# Connection_of_encoders.net
KiCad netlist of a schematic drawn in Altium Designer
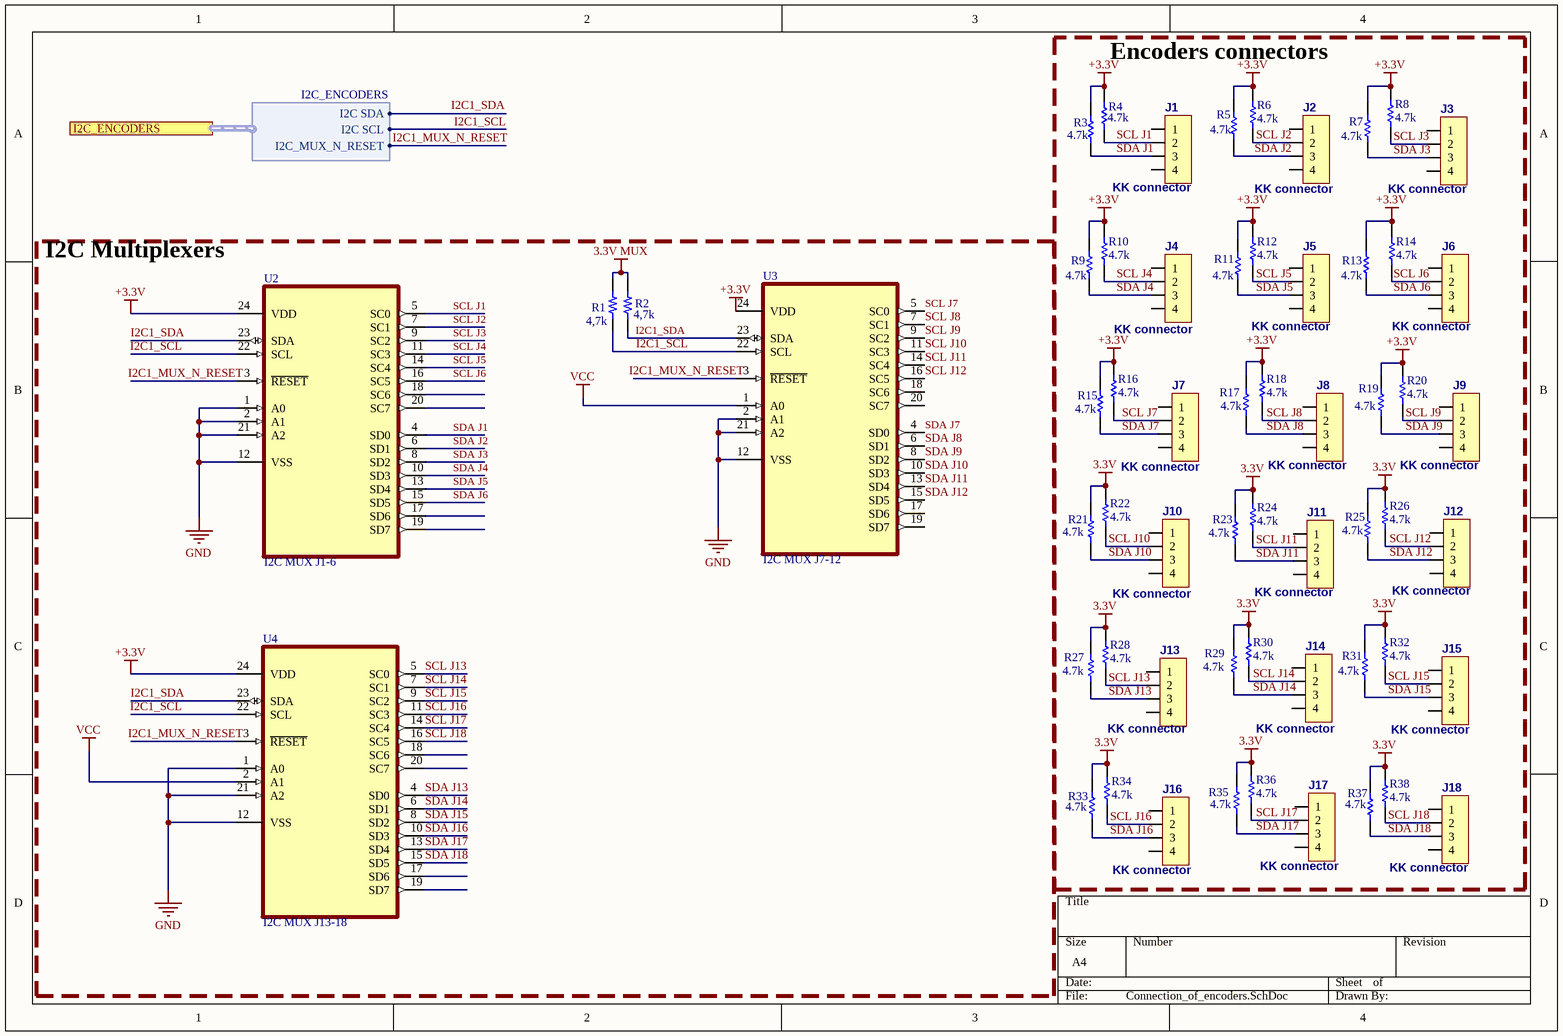
[diagram p0: Connection_of_encoders.SchDoc]

(export (version "E")
  (design (tool "Eeschema 10.0.6"))
  (components
    (comp (ref "J1")
      (value "KK connector")
      (footprint "KK/2.54/4")
      (description "Connector: PCB-cable; KK; socket; male; PIN:4; straight/right-angle; tinned; THT")
      (libsource (lib "kk") (part "CN_4x1"))
    )
    (comp (ref "J2")
      (value "KK connector")
      (footprint "KK/2.54/4")
      (description "Connector: PCB-cable; KK; socket; male; PIN:4; straight/right-angle; tinned; THT")
      (libsource (lib "kk") (part "CN_4x1"))
    )
    (comp (ref "J3")
      (value "KK connector")
      (footprint "KK/2.54/4")
      (description "Connector: PCB-cable; KK; socket; male; PIN:4; straight/right-angle; tinned; THT")
      (libsource (lib "kk") (part "CN_4x1"))
    )
    (comp (ref "J4")
      (value "KK connector")
      (footprint "KK/2.54/4")
      (description "Connector: PCB-cable; KK; socket; male; PIN:4; straight/right-angle; tinned; THT")
      (libsource (lib "kk") (part "CN_4x1"))
    )
    (comp (ref "J5")
      (value "KK connector")
      (footprint "KK/2.54/4")
      (description "Connector: PCB-cable; KK; socket; male; PIN:4; straight/right-angle; tinned; THT")
      (libsource (lib "kk") (part "CN_4x1"))
    )
    (comp (ref "J6")
      (value "KK connector")
      (footprint "KK/2.54/4")
      (description "Connector: PCB-cable; KK; socket; male; PIN:4; straight/right-angle; tinned; THT")
      (libsource (lib "kk") (part "CN_4x1"))
    )
    (comp (ref "J7")
      (value "KK connector")
      (footprint "KK/2.54/4")
      (description "Connector: PCB-cable; KK; socket; male; PIN:4; straight/right-angle; tinned; THT")
      (libsource (lib "kk") (part "CN_4x1"))
    )
    (comp (ref "J8")
      (value "KK connector")
      (footprint "KK/2.54/4")
      (description "Connector: PCB-cable; KK; socket; male; PIN:4; straight/right-angle; tinned; THT")
      (libsource (lib "kk") (part "CN_4x1"))
    )
    (comp (ref "J9")
      (value "KK connector")
      (footprint "KK/2.54/4")
      (description "Connector: PCB-cable; KK; socket; male; PIN:4; straight/right-angle; tinned; THT")
      (libsource (lib "kk") (part "CN_4x1"))
    )
    (comp (ref "J10")
      (value "KK connector")
      (footprint "KK/2.54/4")
      (description "Connector: PCB-cable; KK; socket; male; PIN:4; straight/right-angle; tinned; THT")
      (libsource (lib "kk") (part "CN_4x1"))
    )
    (comp (ref "J11")
      (value "KK connector")
      (footprint "KK/2.54/4")
      (description "Connector: PCB-cable; KK; socket; male; PIN:4; straight/right-angle; tinned; THT")
      (libsource (lib "kk") (part "CN_4x1"))
    )
    (comp (ref "J12")
      (value "KK connector")
      (footprint "KK/2.54/4")
      (description "Connector: PCB-cable; KK; socket; male; PIN:4; straight/right-angle; tinned; THT")
      (libsource (lib "kk") (part "CN_4x1"))
    )
    (comp (ref "J13")
      (value "KK connector")
      (footprint "KK/2.54/4")
      (description "Connector: PCB-cable; KK; socket; male; PIN:4; straight/right-angle; tinned; THT")
      (libsource (lib "kk") (part "CN_4x1"))
    )
    (comp (ref "J14")
      (value "KK connector")
      (footprint "KK/2.54/4")
      (description "Connector: PCB-cable; KK; socket; male; PIN:4; straight/right-angle; tinned; THT")
      (libsource (lib "kk") (part "CN_4x1"))
    )
    (comp (ref "J15")
      (value "KK connector")
      (footprint "KK/2.54/4")
      (description "Connector: PCB-cable; KK; socket; male; PIN:4; straight/right-angle; tinned; THT")
      (libsource (lib "kk") (part "CN_4x1"))
    )
    (comp (ref "J16")
      (value "KK connector")
      (footprint "KK/2.54/4")
      (description "Connector: PCB-cable; KK; socket; male; PIN:4; straight/right-angle; tinned; THT")
      (libsource (lib "kk") (part "CN_4x1"))
    )
    (comp (ref "J17")
      (value "KK connector")
      (footprint "KK/2.54/4")
      (description "Connector: PCB-cable; KK; socket; male; PIN:4; straight/right-angle; tinned; THT")
      (libsource (lib "kk") (part "CN_4x1"))
    )
    (comp (ref "J18")
      (value "KK connector")
      (footprint "KK/2.54/4")
      (description "Connector: PCB-cable; KK; socket; male; PIN:4; straight/right-angle; tinned; THT")
      (libsource (lib "kk") (part "CN_4x1"))
    )
    (comp (ref "R1")
      (value "4,7k")
      (footprint "RES 0603_1608")
      (description "RES 4,7K OHM 1% 0,1W 0603")
      (fields
        (field (name "PART NUMBER") "RNCS0603BKE10K0")
        (field (name "MANUFACTURER") "Stackpole Electronics Inc")
      )
      (libsource (lib "Celestial Altium Library - altium_library") (part "Resistor"))
    )
    (comp (ref "R2")
      (value "4,7k")
      (footprint "RES 0603_1608")
      (description "RES 4,7K OHM 1% 0,1W 0603")
      (fields
        (field (name "PART NUMBER") "RNCS0603BKE10K0")
        (field (name "MANUFACTURER") "Stackpole Electronics Inc")
      )
      (libsource (lib "Celestial Altium Library - altium_library") (part "Resistor"))
    )
    (comp (ref "R3")
      (value "4.7k")
      (footprint "RESC1609X50X30ML10T20")
      (description "RES 4,7K OHM 1% 0,1W 0603 RNCS0603BKE10K0")
      (fields (field (name "PART NUMBER") "CRCW060311K0FKEA") (field (name "MANUFACTURER") "Vishay Dale"))
      (libsource (lib "Altium Content Vault") (part "RES"))
    )
    (comp (ref "R4")
      (value "4.7k")
      (footprint "RESC1609X50X30ML10T20")
      (description "RES 4,7K OHM 1% 0,1W 0603 RNCS0603BKE10K0")
      (fields (field (name "PART NUMBER") "CRCW060311K0FKEA") (field (name "MANUFACTURER") "Vishay Dale"))
      (libsource (lib "Altium Content Vault") (part "RES"))
    )
    (comp (ref "R5")
      (value "4.7k")
      (footprint "RESC1609X50X30ML10T20")
      (description "RES 4,7K OHM 1% 0,1W 0603 RNCS0603BKE10K0")
      (fields (field (name "PART NUMBER") "CRCW060311K0FKEA") (field (name "MANUFACTURER") "Vishay Dale"))
      (libsource (lib "Altium Content Vault") (part "RES"))
    )
    (comp (ref "R6")
      (value "4.7k")
      (footprint "RESC1609X50X30ML10T20")
      (description "RES 4,7K OHM 1% 0,1W 0603 RNCS0603BKE10K0")
      (fields (field (name "PART NUMBER") "CRCW060311K0FKEA") (field (name "MANUFACTURER") "Vishay Dale"))
      (libsource (lib "Altium Content Vault") (part "RES"))
    )
    (comp (ref "R7")
      (value "4.7k")
      (footprint "RESC1609X50X30ML10T20")
      (description "RES 4,7K OHM 1% 0,1W 0603 RNCS0603BKE10K0")
      (fields (field (name "PART NUMBER") "CRCW060311K0FKEA") (field (name "MANUFACTURER") "Vishay Dale"))
      (libsource (lib "Altium Content Vault") (part "RES"))
    )
    (comp (ref "R8")
      (value "4.7k")
      (footprint "RESC1609X50X30ML10T20")
      (description "RES 4,7K OHM 1% 0,1W 0603 RNCS0603BKE10K0")
      (fields (field (name "PART NUMBER") "CRCW060311K0FKEA") (field (name "MANUFACTURER") "Vishay Dale"))
      (libsource (lib "Altium Content Vault") (part "RES"))
    )
    (comp (ref "R9")
      (value "4.7k")
      (footprint "RESC1609X50X30ML10T20")
      (description "RES 4,7K OHM 1% 0,1W 0603 RNCS0603BKE10K0")
      (fields (field (name "PART NUMBER") "CRCW060311K0FKEA") (field (name "MANUFACTURER") "Vishay Dale"))
      (libsource (lib "Altium Content Vault") (part "RES"))
    )
    (comp (ref "R10")
      (value "4.7k")
      (footprint "RESC1609X50X30ML10T20")
      (description "RES 4,7K OHM 1% 0,1W 0603 RNCS0603BKE10K0")
      (fields (field (name "PART NUMBER") "CRCW060311K0FKEA") (field (name "MANUFACTURER") "Vishay Dale"))
      (libsource (lib "Altium Content Vault") (part "RES"))
    )
    (comp (ref "R11")
      (value "4.7k")
      (footprint "RESC1609X50X30ML10T20")
      (description "RES 4,7K OHM 1% 0,1W 0603 RNCS0603BKE10K0")
      (fields (field (name "PART NUMBER") "CRCW060311K0FKEA") (field (name "MANUFACTURER") "Vishay Dale"))
      (libsource (lib "Altium Content Vault") (part "RES"))
    )
    (comp (ref "R12")
      (value "4.7k")
      (footprint "RESC1609X50X30ML10T20")
      (description "RES 4,7K OHM 1% 0,1W 0603 RNCS0603BKE10K0")
      (fields (field (name "PART NUMBER") "CRCW060311K0FKEA") (field (name "MANUFACTURER") "Vishay Dale"))
      (libsource (lib "Altium Content Vault") (part "RES"))
    )
    (comp (ref "R13")
      (value "4.7k")
      (footprint "RESC1609X50X30ML10T20")
      (description "RES 4,7K OHM 1% 0,1W 0603 RNCS0603BKE10K0")
      (fields (field (name "PART NUMBER") "CRCW060311K0FKEA") (field (name "MANUFACTURER") "Vishay Dale"))
      (libsource (lib "Altium Content Vault") (part "RES"))
    )
    (comp (ref "R14")
      (value "4.7k")
      (footprint "RESC1609X50X30ML10T20")
      (description "RES 4,7K OHM 1% 0,1W 0603 RNCS0603BKE10K0")
      (fields (field (name "PART NUMBER") "CRCW060311K0FKEA") (field (name "MANUFACTURER") "Vishay Dale"))
      (libsource (lib "Altium Content Vault") (part "RES"))
    )
    (comp (ref "R15")
      (value "4.7k")
      (footprint "RESC1609X50X30ML10T20")
      (description "RES 4,7K OHM 1% 0,1W 0603 RNCS0603BKE10K0")
      (fields (field (name "PART NUMBER") "CRCW060311K0FKEA") (field (name "MANUFACTURER") "Vishay Dale"))
      (libsource (lib "Altium Content Vault") (part "RES"))
    )
    (comp (ref "R16")
      (value "4.7k")
      (footprint "RESC1609X50X30ML10T20")
      (description "RES 4,7K OHM 1% 0,1W 0603 RNCS0603BKE10K0")
      (fields (field (name "PART NUMBER") "CRCW060311K0FKEA") (field (name "MANUFACTURER") "Vishay Dale"))
      (libsource (lib "Altium Content Vault") (part "RES"))
    )
    (comp (ref "R17")
      (value "4.7k")
      (footprint "RESC1609X50X30ML10T20")
      (description "RES 4,7K OHM 1% 0,1W 0603 RNCS0603BKE10K0")
      (fields (field (name "PART NUMBER") "CRCW060311K0FKEA") (field (name "MANUFACTURER") "Vishay Dale"))
      (libsource (lib "Altium Content Vault") (part "RES"))
    )
    (comp (ref "R18")
      (value "4.7k")
      (footprint "RESC1609X50X30ML10T20")
      (description "RES 4,7K OHM 1% 0,1W 0603 RNCS0603BKE10K0")
      (fields (field (name "PART NUMBER") "CRCW060311K0FKEA") (field (name "MANUFACTURER") "Vishay Dale"))
      (libsource (lib "Altium Content Vault") (part "RES"))
    )
    (comp (ref "R19")
      (value "4.7k")
      (footprint "RESC1609X50X30ML10T20")
      (description "RES 4,7K OHM 1% 0,1W 0603 RNCS0603BKE10K0")
      (fields (field (name "PART NUMBER") "CRCW060311K0FKEA") (field (name "MANUFACTURER") "Vishay Dale"))
      (libsource (lib "Altium Content Vault") (part "RES"))
    )
    (comp (ref "R20")
      (value "4.7k")
      (footprint "RESC1609X50X30ML10T20")
      (description "RES 4,7K OHM 1% 0,1W 0603 RNCS0603BKE10K0")
      (fields (field (name "PART NUMBER") "CRCW060311K0FKEA") (field (name "MANUFACTURER") "Vishay Dale"))
      (libsource (lib "Altium Content Vault") (part "RES"))
    )
    (comp (ref "R21")
      (value "4.7k")
      (footprint "RESC1609X50X30ML10T20")
      (description "RES 4,7K OHM 1% 0,1W 0603 RNCS0603BKE10K0")
      (fields (field (name "PART NUMBER") "CRCW060311K0FKEA") (field (name "MANUFACTURER") "Vishay Dale"))
      (libsource (lib "Altium Content Vault") (part "RES"))
    )
    (comp (ref "R22")
      (value "4.7k")
      (footprint "RESC1609X50X30ML10T20")
      (description "RES 4,7K OHM 1% 0,1W 0603 RNCS0603BKE10K0")
      (fields (field (name "PART NUMBER") "CRCW060311K0FKEA") (field (name "MANUFACTURER") "Vishay Dale"))
      (libsource (lib "Altium Content Vault") (part "RES"))
    )
    (comp (ref "R23")
      (value "4.7k")
      (footprint "RESC1609X50X30ML10T20")
      (description "RES 4,7K OHM 1% 0,1W 0603 RNCS0603BKE10K0")
      (fields (field (name "PART NUMBER") "CRCW060311K0FKEA") (field (name "MANUFACTURER") "Vishay Dale"))
      (libsource (lib "Altium Content Vault") (part "RES"))
    )
    (comp (ref "R24")
      (value "4.7k")
      (footprint "RESC1609X50X30ML10T20")
      (description "RES 4,7K OHM 1% 0,1W 0603 RNCS0603BKE10K0")
      (fields (field (name "PART NUMBER") "CRCW060311K0FKEA") (field (name "MANUFACTURER") "Vishay Dale"))
      (libsource (lib "Altium Content Vault") (part "RES"))
    )
    (comp (ref "R25")
      (value "4.7k")
      (footprint "RESC1609X50X30ML10T20")
      (description "RES 4,7K OHM 1% 0,1W 0603 RNCS0603BKE10K0")
      (fields (field (name "PART NUMBER") "CRCW060311K0FKEA") (field (name "MANUFACTURER") "Vishay Dale"))
      (libsource (lib "Altium Content Vault") (part "RES"))
    )
    (comp (ref "R26")
      (value "4.7k")
      (footprint "RESC1609X50X30ML10T20")
      (description "RES 4,7K OHM 1% 0,1W 0603 RNCS0603BKE10K0")
      (fields (field (name "PART NUMBER") "CRCW060311K0FKEA") (field (name "MANUFACTURER") "Vishay Dale"))
      (libsource (lib "Altium Content Vault") (part "RES"))
    )
    (comp (ref "R27")
      (value "4.7k")
      (footprint "RESC1609X50X30ML10T20")
      (description "RES 4,7K OHM 1% 0,1W 0603 RNCS0603BKE10K0")
      (fields (field (name "PART NUMBER") "CRCW060311K0FKEA") (field (name "MANUFACTURER") "Vishay Dale"))
      (libsource (lib "Altium Content Vault") (part "RES"))
    )
    (comp (ref "R28")
      (value "4.7k")
      (footprint "RESC1609X50X30ML10T20")
      (description "RES 4,7K OHM 1% 0,1W 0603 RNCS0603BKE10K0")
      (fields (field (name "PART NUMBER") "CRCW060311K0FKEA") (field (name "MANUFACTURER") "Vishay Dale"))
      (libsource (lib "Altium Content Vault") (part "RES"))
    )
    (comp (ref "R29")
      (value "4.7k")
      (footprint "RESC1609X50X30ML10T20")
      (description "RES 4,7K OHM 1% 0,1W 0603 RNCS0603BKE10K0")
      (fields (field (name "PART NUMBER") "CRCW060311K0FKEA") (field (name "MANUFACTURER") "Vishay Dale"))
      (libsource (lib "Altium Content Vault") (part "RES"))
    )
    (comp (ref "R30")
      (value "4.7k")
      (footprint "RESC1609X50X30ML10T20")
      (description "RES 4,7K OHM 1% 0,1W 0603 RNCS0603BKE10K0")
      (fields (field (name "PART NUMBER") "CRCW060311K0FKEA") (field (name "MANUFACTURER") "Vishay Dale"))
      (libsource (lib "Altium Content Vault") (part "RES"))
    )
    (comp (ref "R31")
      (value "4.7k")
      (footprint "RESC1609X50X30ML10T20")
      (description "RES 4,7K OHM 1% 0,1W 0603 RNCS0603BKE10K0")
      (fields (field (name "PART NUMBER") "CRCW060311K0FKEA") (field (name "MANUFACTURER") "Vishay Dale"))
      (libsource (lib "Altium Content Vault") (part "RES"))
    )
    (comp (ref "R32")
      (value "4.7k")
      (footprint "RESC1609X50X30ML10T20")
      (description "RES 4,7K OHM 1% 0,1W 0603 RNCS0603BKE10K0")
      (fields (field (name "PART NUMBER") "CRCW060311K0FKEA") (field (name "MANUFACTURER") "Vishay Dale"))
      (libsource (lib "Altium Content Vault") (part "RES"))
    )
    (comp (ref "R33")
      (value "4.7k")
      (footprint "RESC1609X50X30ML10T20")
      (description "RES 4,7K OHM 1% 0,1W 0603 RNCS0603BKE10K0")
      (fields (field (name "PART NUMBER") "CRCW060311K0FKEA") (field (name "MANUFACTURER") "Vishay Dale"))
      (libsource (lib "Altium Content Vault") (part "RES"))
    )
    (comp (ref "R34")
      (value "4.7k")
      (footprint "RESC1609X50X30ML10T20")
      (description "RES 4,7K OHM 1% 0,1W 0603 RNCS0603BKE10K0")
      (fields (field (name "PART NUMBER") "CRCW060311K0FKEA") (field (name "MANUFACTURER") "Vishay Dale"))
      (libsource (lib "Altium Content Vault") (part "RES"))
    )
    (comp (ref "R35")
      (value "4.7k")
      (footprint "RESC1609X50X30ML10T20")
      (description "RES 4,7K OHM 1% 0,1W 0603 RNCS0603BKE10K0")
      (fields (field (name "PART NUMBER") "CRCW060311K0FKEA") (field (name "MANUFACTURER") "Vishay Dale"))
      (libsource (lib "Altium Content Vault") (part "RES"))
    )
    (comp (ref "R36")
      (value "4.7k")
      (footprint "RESC1609X50X30ML10T20")
      (description "RES 4,7K OHM 1% 0,1W 0603 RNCS0603BKE10K0")
      (fields (field (name "PART NUMBER") "CRCW060311K0FKEA") (field (name "MANUFACTURER") "Vishay Dale"))
      (libsource (lib "Altium Content Vault") (part "RES"))
    )
    (comp (ref "R37")
      (value "4.7k")
      (footprint "RESC1609X50X30ML10T20")
      (description "RES 4,7K OHM 1% 0,1W 0603 RNCS0603BKE10K0")
      (fields (field (name "PART NUMBER") "CRCW060311K0FKEA") (field (name "MANUFACTURER") "Vishay Dale"))
      (libsource (lib "Altium Content Vault") (part "RES"))
    )
    (comp (ref "R38")
      (value "4.7k")
      (footprint "RESC1609X50X30ML10T20")
      (description "RES 4,7K OHM 1% 0,1W 0603 RNCS0603BKE10K0")
      (fields (field (name "PART NUMBER") "CRCW060311K0FKEA") (field (name "MANUFACTURER") "Vishay Dale"))
      (libsource (lib "Altium Content Vault") (part "RES"))
    )
    (comp (ref "U2")
      (value "I2C MUX J1-6")
      (footprint "SOP65P640X110-24N")
      (description "Translating Multiplexer Interface 24-TSSOP PCA9547PW,118")
      (fields (field (name "MP") "PCA9547PW,118") (field (name "MF") "NXP USA"))
      (libsource (lib "MyWorkspace") (part "PCA9547PW,118"))
    )
    (comp (ref "U3")
      (value "I2C MUX J7-12")
      (footprint "SOP65P640X110-24N")
      (description "Translating Multiplexer Interface 24-TSSOP PCA9547PW,118")
      (fields (field (name "MP") "PCA9547PW,118") (field (name "MF") "NXP USA"))
      (libsource (lib "MyWorkspace") (part "PCA9547PW,118"))
    )
    (comp (ref "U4")
      (value "I2C MUX J13-18")
      (footprint "SOP65P640X110-24N")
      (description "Translating Multiplexer Interface 24-TSSOP PCA9547PW")
      (fields (field (name "MP") "PCA9547PW,118") (field (name "MF") "NXP USA"))
      (libsource (lib "MyWorkspace") (part "PCA9547PW,118"))
    )
  )
  (nets
    (net (code "2") (name "+3.3V") (class "Default")
      (node (ref "R10") (pin "2") (pinfunction "2_2") (pintype "passive"))
      (node (ref "R11") (pin "2") (pinfunction "2_2") (pintype "passive"))
      (node (ref "R12") (pin "2") (pinfunction "2_2") (pintype "passive"))
      (node (ref "R13") (pin "2") (pinfunction "2_2") (pintype "passive"))
      (node (ref "R14") (pin "2") (pinfunction "2_2") (pintype "passive"))
      (node (ref "R15") (pin "2") (pinfunction "2_2") (pintype "passive"))
      (node (ref "R16") (pin "2") (pinfunction "2_2") (pintype "passive"))
      (node (ref "R17") (pin "2") (pinfunction "2_2") (pintype "passive"))
      (node (ref "R18") (pin "2") (pinfunction "2_2") (pintype "passive"))
      (node (ref "R19") (pin "2") (pinfunction "2_2") (pintype "passive"))
      (node (ref "R20") (pin "2") (pinfunction "2_2") (pintype "passive"))
      (node (ref "R3") (pin "2") (pinfunction "2_2") (pintype "passive"))
      (node (ref "R4") (pin "2") (pinfunction "2_2") (pintype "passive"))
      (node (ref "R5") (pin "2") (pinfunction "2_2") (pintype "passive"))
      (node (ref "R6") (pin "2") (pinfunction "2_2") (pintype "passive"))
      (node (ref "R7") (pin "2") (pinfunction "2_2") (pintype "passive"))
      (node (ref "R8") (pin "2") (pinfunction "2_2") (pintype "passive"))
      (node (ref "R9") (pin "2") (pinfunction "2_2") (pintype "passive"))
      (node (ref "U2") (pin "24") (pinfunction "VDD_24") (pintype "power_in"))
      (node (ref "U3") (pin "24") (pinfunction "VDD_24") (pintype "power_in"))
      (node (ref "U4") (pin "24") (pinfunction "VDD_24") (pintype "power_in"))
    )
    (net (code "3") (name "/I2C1_MUX_N_RESET") (class "Default")
      (node (ref "U2") (pin "3") (pinfunction "~{RESET}_3") (pintype "input"))
      (node (ref "U3") (pin "3") (pinfunction "~{RESET}_3") (pintype "input"))
      (node (ref "U4") (pin "3") (pinfunction "~{RESET}_3") (pintype "input"))
    )
    (net (code "4") (name "/I2C1_SCL") (class "Default")
      (node (ref "R1") (pin "2") (pinfunction "2_2") (pintype "passive"))
      (node (ref "U2") (pin "22") (pinfunction "SCL_22") (pintype "input"))
      (node (ref "U3") (pin "22") (pinfunction "SCL_22") (pintype "input"))
      (node (ref "U4") (pin "22") (pinfunction "SCL_22") (pintype "input"))
    )
    (net (code "5") (name "/I2C1_SDA") (class "Default")
      (node (ref "R2") (pin "2") (pinfunction "2_2") (pintype "passive"))
      (node (ref "U2") (pin "23") (pinfunction "SDA_23") (pintype "bidirectional"))
      (node (ref "U3") (pin "23") (pinfunction "SDA_23") (pintype "bidirectional"))
      (node (ref "U4") (pin "23") (pinfunction "SDA_23") (pintype "bidirectional"))
    )
    (net (code "6") (name "/SCL J1") (class "Default")
      (node (ref "J1") (pin "2") (pinfunction "2_2") (pintype "passive"))
      (node (ref "R4") (pin "1") (pinfunction "1_1") (pintype "passive"))
      (node (ref "U2") (pin "5") (pinfunction "SC0_5") (pintype "output"))
    )
    (net (code "7") (name "/SCL J2") (class "Default")
      (node (ref "J2") (pin "2") (pinfunction "2_2") (pintype "passive"))
      (node (ref "R6") (pin "1") (pinfunction "1_1") (pintype "passive"))
      (node (ref "U2") (pin "7") (pinfunction "SC1_7") (pintype "output"))
    )
    (net (code "8") (name "/SCL J3") (class "Default")
      (node (ref "J3") (pin "2") (pinfunction "2_2") (pintype "passive"))
      (node (ref "R8") (pin "1") (pinfunction "1_1") (pintype "passive"))
      (node (ref "U2") (pin "9") (pinfunction "SC2_9") (pintype "output"))
    )
    (net (code "9") (name "/SCL J4") (class "Default")
      (node (ref "J4") (pin "2") (pinfunction "2_2") (pintype "passive"))
      (node (ref "R10") (pin "1") (pinfunction "1_1") (pintype "passive"))
      (node (ref "U2") (pin "11") (pinfunction "SC3_11") (pintype "output"))
    )
    (net (code "10") (name "/SCL J5") (class "Default")
      (node (ref "J5") (pin "2") (pinfunction "2_2") (pintype "passive"))
      (node (ref "R12") (pin "1") (pinfunction "1_1") (pintype "passive"))
      (node (ref "U2") (pin "14") (pinfunction "SC4_14") (pintype "output"))
    )
    (net (code "11") (name "/SCL J6") (class "Default")
      (node (ref "J6") (pin "2") (pinfunction "2_2") (pintype "passive"))
      (node (ref "R14") (pin "1") (pinfunction "1_1") (pintype "passive"))
      (node (ref "U2") (pin "16") (pinfunction "SC5_16") (pintype "output"))
    )
    (net (code "12") (name "/SCL J7") (class "Default")
      (node (ref "J7") (pin "2") (pinfunction "2_2") (pintype "passive"))
      (node (ref "R16") (pin "1") (pinfunction "1_1") (pintype "passive"))
      (node (ref "U3") (pin "5") (pinfunction "SC0_5") (pintype "output"))
    )
    (net (code "13") (name "/SCL J8") (class "Default")
      (node (ref "J8") (pin "2") (pinfunction "2_2") (pintype "passive"))
      (node (ref "R18") (pin "1") (pinfunction "1_1") (pintype "passive"))
      (node (ref "U3") (pin "7") (pinfunction "SC1_7") (pintype "output"))
    )
    (net (code "14") (name "/SCL J9") (class "Default")
      (node (ref "J9") (pin "2") (pinfunction "2_2") (pintype "passive"))
      (node (ref "R20") (pin "1") (pinfunction "1_1") (pintype "passive"))
      (node (ref "U3") (pin "9") (pinfunction "SC2_9") (pintype "output"))
    )
    (net (code "15") (name "/SCL J10") (class "Default")
      (node (ref "J10") (pin "2") (pinfunction "2_2") (pintype "passive"))
      (node (ref "R22") (pin "1") (pinfunction "1_1") (pintype "passive"))
      (node (ref "U3") (pin "11") (pinfunction "SC3_11") (pintype "output"))
    )
    (net (code "16") (name "/SCL J11") (class "Default")
      (node (ref "J11") (pin "2") (pinfunction "2_2") (pintype "passive"))
      (node (ref "R24") (pin "1") (pinfunction "1_1") (pintype "passive"))
      (node (ref "U3") (pin "14") (pinfunction "SC4_14") (pintype "output"))
    )
    (net (code "17") (name "/SCL J12") (class "Default")
      (node (ref "J12") (pin "2") (pinfunction "2_2") (pintype "passive"))
      (node (ref "R26") (pin "1") (pinfunction "1_1") (pintype "passive"))
      (node (ref "U3") (pin "16") (pinfunction "SC5_16") (pintype "output"))
    )
    (net (code "18") (name "/SCL J13") (class "Default")
      (node (ref "J13") (pin "2") (pinfunction "2_2") (pintype "passive"))
      (node (ref "R28") (pin "1") (pinfunction "1_1") (pintype "passive"))
      (node (ref "U4") (pin "5") (pinfunction "SC0_5") (pintype "output"))
    )
    (net (code "19") (name "/SCL J14") (class "Default")
      (node (ref "J14") (pin "2") (pinfunction "2_2") (pintype "passive"))
      (node (ref "R30") (pin "1") (pinfunction "1_1") (pintype "passive"))
      (node (ref "U4") (pin "7") (pinfunction "SC1_7") (pintype "output"))
    )
    (net (code "20") (name "/SCL J15") (class "Default")
      (node (ref "J15") (pin "2") (pinfunction "2_2") (pintype "passive"))
      (node (ref "R32") (pin "1") (pinfunction "1_1") (pintype "passive"))
      (node (ref "U4") (pin "9") (pinfunction "SC2_9") (pintype "output"))
    )
    (net (code "21") (name "/SCL J16") (class "Default")
      (node (ref "J16") (pin "2") (pinfunction "2_2") (pintype "passive"))
      (node (ref "R34") (pin "1") (pinfunction "1_1") (pintype "passive"))
      (node (ref "U4") (pin "11") (pinfunction "SC3_11") (pintype "output"))
    )
    (net (code "22") (name "/SCL J17") (class "Default")
      (node (ref "J17") (pin "2") (pinfunction "2_2") (pintype "passive"))
      (node (ref "R36") (pin "1") (pinfunction "1_1") (pintype "passive"))
      (node (ref "U4") (pin "14") (pinfunction "SC4_14") (pintype "output"))
    )
    (net (code "23") (name "/SCL J18") (class "Default")
      (node (ref "J18") (pin "2") (pinfunction "2_2") (pintype "passive"))
      (node (ref "R38") (pin "1") (pinfunction "1_1") (pintype "passive"))
      (node (ref "U4") (pin "16") (pinfunction "SC5_16") (pintype "output"))
    )
    (net (code "24") (name "/SDA J1") (class "Default")
      (node (ref "J1") (pin "3") (pinfunction "3_3") (pintype "passive"))
      (node (ref "R3") (pin "1") (pinfunction "1_1") (pintype "passive"))
      (node (ref "U2") (pin "4") (pinfunction "SD0_4") (pintype "output"))
    )
    (net (code "25") (name "/SDA J2") (class "Default")
      (node (ref "J2") (pin "3") (pinfunction "3_3") (pintype "passive"))
      (node (ref "R5") (pin "1") (pinfunction "1_1") (pintype "passive"))
      (node (ref "U2") (pin "6") (pinfunction "SD1_6") (pintype "output"))
    )
    (net (code "26") (name "/SDA J3") (class "Default")
      (node (ref "J3") (pin "3") (pinfunction "3_3") (pintype "passive"))
      (node (ref "R7") (pin "1") (pinfunction "1_1") (pintype "passive"))
      (node (ref "U2") (pin "8") (pinfunction "SD2_8") (pintype "output"))
    )
    (net (code "27") (name "/SDA J4") (class "Default")
      (node (ref "J4") (pin "3") (pinfunction "3_3") (pintype "passive"))
      (node (ref "R9") (pin "1") (pinfunction "1_1") (pintype "passive"))
      (node (ref "U2") (pin "10") (pinfunction "SD3_10") (pintype "output"))
    )
    (net (code "28") (name "/SDA J5") (class "Default")
      (node (ref "J5") (pin "3") (pinfunction "3_3") (pintype "passive"))
      (node (ref "R11") (pin "1") (pinfunction "1_1") (pintype "passive"))
      (node (ref "U2") (pin "13") (pinfunction "SD4_13") (pintype "output"))
    )
    (net (code "29") (name "/SDA J6") (class "Default")
      (node (ref "J6") (pin "3") (pinfunction "3_3") (pintype "passive"))
      (node (ref "R13") (pin "1") (pinfunction "1_1") (pintype "passive"))
      (node (ref "U2") (pin "15") (pinfunction "SD5_15") (pintype "output"))
    )
    (net (code "30") (name "/SDA J7") (class "Default")
      (node (ref "J7") (pin "3") (pinfunction "3_3") (pintype "passive"))
      (node (ref "R15") (pin "1") (pinfunction "1_1") (pintype "passive"))
      (node (ref "U3") (pin "4") (pinfunction "SD0_4") (pintype "output"))
    )
    (net (code "31") (name "/SDA J8") (class "Default")
      (node (ref "J8") (pin "3") (pinfunction "3_3") (pintype "passive"))
      (node (ref "R17") (pin "1") (pinfunction "1_1") (pintype "passive"))
      (node (ref "U3") (pin "6") (pinfunction "SD1_6") (pintype "output"))
    )
    (net (code "32") (name "/SDA J9") (class "Default")
      (node (ref "J9") (pin "3") (pinfunction "3_3") (pintype "passive"))
      (node (ref "R19") (pin "1") (pinfunction "1_1") (pintype "passive"))
      (node (ref "U3") (pin "8") (pinfunction "SD2_8") (pintype "output"))
    )
    (net (code "33") (name "/SDA J10") (class "Default")
      (node (ref "J10") (pin "3") (pinfunction "3_3") (pintype "passive"))
      (node (ref "R21") (pin "1") (pinfunction "1_1") (pintype "passive"))
      (node (ref "U3") (pin "10") (pinfunction "SD3_10") (pintype "output"))
    )
    (net (code "34") (name "/SDA J11") (class "Default")
      (node (ref "J11") (pin "3") (pinfunction "3_3") (pintype "passive"))
      (node (ref "R23") (pin "1") (pinfunction "1_1") (pintype "passive"))
      (node (ref "U3") (pin "13") (pinfunction "SD4_13") (pintype "output"))
    )
    (net (code "35") (name "/SDA J12") (class "Default")
      (node (ref "J12") (pin "3") (pinfunction "3_3") (pintype "passive"))
      (node (ref "R25") (pin "1") (pinfunction "1_1") (pintype "passive"))
      (node (ref "U3") (pin "15") (pinfunction "SD5_15") (pintype "output"))
    )
    (net (code "36") (name "/SDA J13") (class "Default")
      (node (ref "J13") (pin "3") (pinfunction "3_3") (pintype "passive"))
      (node (ref "R27") (pin "1") (pinfunction "1_1") (pintype "passive"))
      (node (ref "U4") (pin "4") (pinfunction "SD0_4") (pintype "output"))
    )
    (net (code "37") (name "/SDA J14") (class "Default")
      (node (ref "J14") (pin "3") (pinfunction "3_3") (pintype "passive"))
      (node (ref "R29") (pin "1") (pinfunction "1_1") (pintype "passive"))
      (node (ref "U4") (pin "6") (pinfunction "SD1_6") (pintype "output"))
    )
    (net (code "38") (name "/SDA J15") (class "Default")
      (node (ref "J15") (pin "3") (pinfunction "3_3") (pintype "passive"))
      (node (ref "R31") (pin "1") (pinfunction "1_1") (pintype "passive"))
      (node (ref "U4") (pin "8") (pinfunction "SD2_8") (pintype "output"))
    )
    (net (code "39") (name "/SDA J16") (class "Default")
      (node (ref "J16") (pin "3") (pinfunction "3_3") (pintype "passive"))
      (node (ref "R33") (pin "1") (pinfunction "1_1") (pintype "passive"))
      (node (ref "U4") (pin "10") (pinfunction "SD3_10") (pintype "output"))
    )
    (net (code "40") (name "/SDA J17") (class "Default")
      (node (ref "J17") (pin "3") (pinfunction "3_3") (pintype "passive"))
      (node (ref "R35") (pin "1") (pinfunction "1_1") (pintype "passive"))
      (node (ref "U4") (pin "13") (pinfunction "SD4_13") (pintype "output"))
    )
    (net (code "41") (name "/SDA J18") (class "Default")
      (node (ref "J18") (pin "3") (pinfunction "3_3") (pintype "passive"))
      (node (ref "R37") (pin "1") (pinfunction "1_1") (pintype "passive"))
      (node (ref "U4") (pin "15") (pinfunction "SD5_15") (pintype "output"))
    )
    (net (code "43") (name "3.3V") (class "Default")
      (node (ref "R21") (pin "2") (pinfunction "2_2") (pintype "passive"))
      (node (ref "R22") (pin "2") (pinfunction "2_2") (pintype "passive"))
      (node (ref "R23") (pin "2") (pinfunction "2_2") (pintype "passive"))
      (node (ref "R24") (pin "2") (pinfunction "2_2") (pintype "passive"))
      (node (ref "R25") (pin "2") (pinfunction "2_2") (pintype "passive"))
      (node (ref "R26") (pin "2") (pinfunction "2_2") (pintype "passive"))
      (node (ref "R27") (pin "2") (pinfunction "2_2") (pintype "passive"))
      (node (ref "R28") (pin "2") (pinfunction "2_2") (pintype "passive"))
      (node (ref "R29") (pin "2") (pinfunction "2_2") (pintype "passive"))
      (node (ref "R30") (pin "2") (pinfunction "2_2") (pintype "passive"))
      (node (ref "R31") (pin "2") (pinfunction "2_2") (pintype "passive"))
      (node (ref "R32") (pin "2") (pinfunction "2_2") (pintype "passive"))
      (node (ref "R33") (pin "2") (pinfunction "2_2") (pintype "passive"))
      (node (ref "R34") (pin "2") (pinfunction "2_2") (pintype "passive"))
      (node (ref "R35") (pin "2") (pinfunction "2_2") (pintype "passive"))
      (node (ref "R36") (pin "2") (pinfunction "2_2") (pintype "passive"))
      (node (ref "R37") (pin "2") (pinfunction "2_2") (pintype "passive"))
      (node (ref "R38") (pin "2") (pinfunction "2_2") (pintype "passive"))
    )
    (net (code "44") (name "3.3V MUX") (class "Default")
      (node (ref "R1") (pin "1") (pinfunction "1_1") (pintype "passive"))
      (node (ref "R2") (pin "1") (pinfunction "1_1") (pintype "passive"))
    )
    (net (code "45") (name "GND") (class "Default")
      (node (ref "U2") (pin "1") (pinfunction "A0_1") (pintype "input"))
      (node (ref "U2") (pin "12") (pinfunction "VSS_12") (pintype "passive"))
      (node (ref "U2") (pin "2") (pinfunction "A1_2") (pintype "input"))
      (node (ref "U2") (pin "21") (pinfunction "A2_21") (pintype "input"))
      (node (ref "U3") (pin "12") (pinfunction "VSS_12") (pintype "passive"))
      (node (ref "U3") (pin "2") (pinfunction "A1_2") (pintype "input"))
      (node (ref "U3") (pin "21") (pinfunction "A2_21") (pintype "input"))
      (node (ref "U4") (pin "1") (pinfunction "A0_1") (pintype "input"))
      (node (ref "U4") (pin "12") (pinfunction "VSS_12") (pintype "passive"))
      (node (ref "U4") (pin "21") (pinfunction "A2_21") (pintype "input"))
    )
    (net (code "46") (name "VCC") (class "Default")
      (node (ref "U3") (pin "1") (pinfunction "A0_1") (pintype "input"))
      (node (ref "U4") (pin "2") (pinfunction "A1_2") (pintype "input"))
    )
    (net (code "47") (name "unconnected-(J1-Pad1)") (class "Default")
      (node (ref "J1") (pin "1") (pinfunction "1_1") (pintype "passive"))
    )
    (net (code "48") (name "unconnected-(J1-Pad4)") (class "Default")
      (node (ref "J1") (pin "4") (pinfunction "4_4") (pintype "passive"))
    )
    (net (code "49") (name "unconnected-(J2-Pad1)") (class "Default")
      (node (ref "J2") (pin "1") (pinfunction "1_1") (pintype "passive"))
    )
    (net (code "50") (name "unconnected-(J2-Pad4)") (class "Default")
      (node (ref "J2") (pin "4") (pinfunction "4_4") (pintype "passive"))
    )
    (net (code "51") (name "unconnected-(J3-Pad1)") (class "Default")
      (node (ref "J3") (pin "1") (pinfunction "1_1") (pintype "passive"))
    )
    (net (code "52") (name "unconnected-(J3-Pad4)") (class "Default")
      (node (ref "J3") (pin "4") (pinfunction "4_4") (pintype "passive"))
    )
    (net (code "53") (name "unconnected-(J4-Pad1)") (class "Default")
      (node (ref "J4") (pin "1") (pinfunction "1_1") (pintype "passive"))
    )
    (net (code "54") (name "unconnected-(J4-Pad4)") (class "Default")
      (node (ref "J4") (pin "4") (pinfunction "4_4") (pintype "passive"))
    )
    (net (code "55") (name "unconnected-(J5-Pad1)") (class "Default")
      (node (ref "J5") (pin "1") (pinfunction "1_1") (pintype "passive"))
    )
    (net (code "56") (name "unconnected-(J5-Pad4)") (class "Default")
      (node (ref "J5") (pin "4") (pinfunction "4_4") (pintype "passive"))
    )
    (net (code "57") (name "unconnected-(J6-Pad1)") (class "Default")
      (node (ref "J6") (pin "1") (pinfunction "1_1") (pintype "passive"))
    )
    (net (code "58") (name "unconnected-(J6-Pad4)") (class "Default")
      (node (ref "J6") (pin "4") (pinfunction "4_4") (pintype "passive"))
    )
    (net (code "59") (name "unconnected-(J7-Pad1)") (class "Default")
      (node (ref "J7") (pin "1") (pinfunction "1_1") (pintype "passive"))
    )
    (net (code "60") (name "unconnected-(J7-Pad4)") (class "Default")
      (node (ref "J7") (pin "4") (pinfunction "4_4") (pintype "passive"))
    )
    (net (code "61") (name "unconnected-(J8-Pad1)") (class "Default")
      (node (ref "J8") (pin "1") (pinfunction "1_1") (pintype "passive"))
    )
    (net (code "62") (name "unconnected-(J8-Pad4)") (class "Default")
      (node (ref "J8") (pin "4") (pinfunction "4_4") (pintype "passive"))
    )
    (net (code "63") (name "unconnected-(J9-Pad1)") (class "Default")
      (node (ref "J9") (pin "1") (pinfunction "1_1") (pintype "passive"))
    )
    (net (code "64") (name "unconnected-(J9-Pad4)") (class "Default")
      (node (ref "J9") (pin "4") (pinfunction "4_4") (pintype "passive"))
    )
    (net (code "65") (name "unconnected-(J10-Pad1)") (class "Default")
      (node (ref "J10") (pin "1") (pinfunction "1_1") (pintype "passive"))
    )
    (net (code "66") (name "unconnected-(J10-Pad4)") (class "Default")
      (node (ref "J10") (pin "4") (pinfunction "4_4") (pintype "passive"))
    )
    (net (code "67") (name "unconnected-(J11-Pad1)") (class "Default")
      (node (ref "J11") (pin "1") (pinfunction "1_1") (pintype "passive"))
    )
    (net (code "68") (name "unconnected-(J11-Pad4)") (class "Default")
      (node (ref "J11") (pin "4") (pinfunction "4_4") (pintype "passive"))
    )
    (net (code "69") (name "unconnected-(J12-Pad1)") (class "Default")
      (node (ref "J12") (pin "1") (pinfunction "1_1") (pintype "passive"))
    )
    (net (code "70") (name "unconnected-(J12-Pad4)") (class "Default")
      (node (ref "J12") (pin "4") (pinfunction "4_4") (pintype "passive"))
    )
    (net (code "71") (name "unconnected-(J13-Pad1)") (class "Default")
      (node (ref "J13") (pin "1") (pinfunction "1_1") (pintype "passive"))
    )
    (net (code "72") (name "unconnected-(J13-Pad4)") (class "Default")
      (node (ref "J13") (pin "4") (pinfunction "4_4") (pintype "passive"))
    )
    (net (code "73") (name "unconnected-(J14-Pad1)") (class "Default")
      (node (ref "J14") (pin "1") (pinfunction "1_1") (pintype "passive"))
    )
    (net (code "74") (name "unconnected-(J14-Pad4)") (class "Default")
      (node (ref "J14") (pin "4") (pinfunction "4_4") (pintype "passive"))
    )
    (net (code "75") (name "unconnected-(J15-Pad1)") (class "Default")
      (node (ref "J15") (pin "1") (pinfunction "1_1") (pintype "passive"))
    )
    (net (code "76") (name "unconnected-(J15-Pad4)") (class "Default")
      (node (ref "J15") (pin "4") (pinfunction "4_4") (pintype "passive"))
    )
    (net (code "77") (name "unconnected-(J16-Pad1)") (class "Default")
      (node (ref "J16") (pin "1") (pinfunction "1_1") (pintype "passive"))
    )
    (net (code "78") (name "unconnected-(J16-Pad4)") (class "Default")
      (node (ref "J16") (pin "4") (pinfunction "4_4") (pintype "passive"))
    )
    (net (code "79") (name "unconnected-(J17-Pad1)") (class "Default")
      (node (ref "J17") (pin "1") (pinfunction "1_1") (pintype "passive"))
    )
    (net (code "80") (name "unconnected-(J17-Pad4)") (class "Default")
      (node (ref "J17") (pin "4") (pinfunction "4_4") (pintype "passive"))
    )
    (net (code "81") (name "unconnected-(J18-Pad1)") (class "Default")
      (node (ref "J18") (pin "1") (pinfunction "1_1") (pintype "passive"))
    )
    (net (code "82") (name "unconnected-(J18-Pad4)") (class "Default")
      (node (ref "J18") (pin "4") (pinfunction "4_4") (pintype "passive"))
    )
    (net (code "83") (name "unconnected-(U2-SC6-Pad18)") (class "Default")
      (node (ref "U2") (pin "18") (pinfunction "SC6_18") (pintype "output"))
    )
    (net (code "84") (name "unconnected-(U2-SC7-Pad20)") (class "Default")
      (node (ref "U2") (pin "20") (pinfunction "SC7_20") (pintype "output"))
    )
    (net (code "85") (name "unconnected-(U2-SD6-Pad17)") (class "Default")
      (node (ref "U2") (pin "17") (pinfunction "SD6_17") (pintype "output"))
    )
    (net (code "86") (name "unconnected-(U2-SD7-Pad19)") (class "Default")
      (node (ref "U2") (pin "19") (pinfunction "SD7_19") (pintype "output"))
    )
    (net (code "87") (name "unconnected-(U3-SC6-Pad18)") (class "Default")
      (node (ref "U3") (pin "18") (pinfunction "SC6_18") (pintype "output"))
    )
    (net (code "88") (name "unconnected-(U3-SC7-Pad20)") (class "Default")
      (node (ref "U3") (pin "20") (pinfunction "SC7_20") (pintype "output"))
    )
    (net (code "89") (name "unconnected-(U3-SD6-Pad17)") (class "Default")
      (node (ref "U3") (pin "17") (pinfunction "SD6_17") (pintype "output"))
    )
    (net (code "90") (name "unconnected-(U3-SD7-Pad19)") (class "Default")
      (node (ref "U3") (pin "19") (pinfunction "SD7_19") (pintype "output"))
    )
    (net (code "91") (name "unconnected-(U4-SC6-Pad18)") (class "Default")
      (node (ref "U4") (pin "18") (pinfunction "SC6_18") (pintype "output"))
    )
    (net (code "92") (name "unconnected-(U4-SC7-Pad20)") (class "Default")
      (node (ref "U4") (pin "20") (pinfunction "SC7_20") (pintype "output"))
    )
    (net (code "93") (name "unconnected-(U4-SD6-Pad17)") (class "Default")
      (node (ref "U4") (pin "17") (pinfunction "SD6_17") (pintype "output"))
    )
    (net (code "94") (name "unconnected-(U4-SD7-Pad19)") (class "Default")
      (node (ref "U4") (pin "19") (pinfunction "SD7_19") (pintype "output"))
    )
  )
)
